# JHZ-E01S-HW-Sensor-H-I-S0_1.net
KiCad netlist of a schematic drawn in Altium Designer
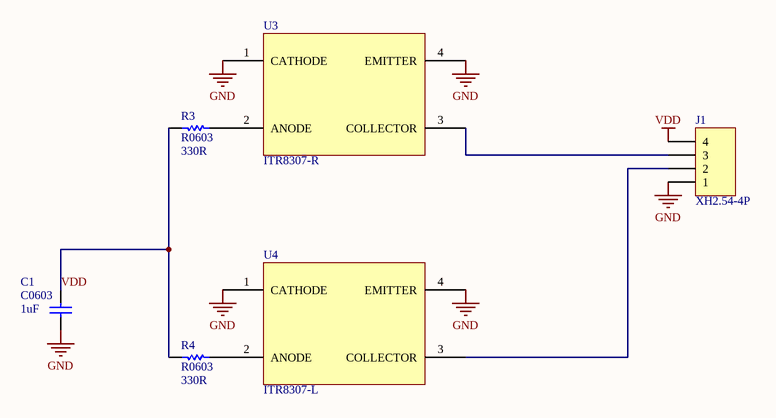
[diagram p0: JHZ-E01S-HW-Sensor-H-I-S0.1.SchDoc]

(export (version "E")
  (design (tool "Eeschema 10.0.6"))
  (components
    (comp (ref "C1")
      (value "C0603")
      (footprint "C0603_M1608")
      (description "Capacitor")
      (fields (field (name "ALTIUM_VALUE") "1uF") (field (name "PUBLISHER") "Altium Limited"))
      (libsource (lib "Miscellaneous Devices") (part "Cap"))
    )
    (comp (ref "J1")
      (value "XH2.54-4P")
      (footprint "PH-AWB-4P")
      (description "插座XH2.54-4P")
      (fields (field (name "Comment") "PH-AWB-4P") (field (name "PUBLISHER") "Altium Limited"))
      (libsource (lib "Liyao原理图库") (part "XH2.54-4P"))
    )
    (comp (ref "R3")
      (value "R0603")
      (description "Resistor")
      (fields (field (name "ALTIUM_VALUE") "330R") (field (name "PUBLISHER") "Altium Limited"))
      (libsource (lib "Miscellaneous Devices") (part "Res1"))
    )
    (comp (ref "R4")
      (value "R0603")
      (description "Resistor")
      (fields (field (name "ALTIUM_VALUE") "330R") (field (name "PUBLISHER") "Altium Limited"))
      (libsource (lib "Miscellaneous Devices") (part "Res1"))
    )
    (comp (ref "U3") (value "ITR8307-R") (footprint "ITR8307") (libsource (lib "光电管") (part "Component_1")))
    (comp (ref "U4") (value "ITR8307-L") (footprint "ITR8307") (libsource (lib "光电管") (part "Component_1")))
  )
  (nets
    (net (code "1") (name "GND") (class "Default")
      (node (ref "C1") (pin "2") (pinfunction "2_2") (pintype "passive"))
      (node (ref "J1") (pin "1") (pinfunction "1_1") (pintype "passive"))
      (node (ref "U3") (pin "1") (pinfunction "CATHODE_1") (pintype "passive"))
      (node (ref "U3") (pin "4") (pinfunction "EMITTER_4") (pintype "passive"))
      (node (ref "U4") (pin "1") (pinfunction "CATHODE_1") (pintype "passive"))
      (node (ref "U4") (pin "4") (pinfunction "EMITTER_4") (pintype "passive"))
    )
    (net (code "2") (name "Net-(U3-ANODE)") (class "Default")
      (node (ref "R3") (pin "1") (pinfunction "1_1") (pintype "passive"))
      (node (ref "U3") (pin "2") (pinfunction "ANODE_2") (pintype "passive"))
    )
    (net (code "3") (name "Net-(U3-COLLECTOR)") (class "Default")
      (node (ref "J1") (pin "3") (pinfunction "3_3") (pintype "passive"))
      (node (ref "U3") (pin "3") (pinfunction "COLLECTOR_3") (pintype "passive"))
    )
    (net (code "4") (name "Net-(U4-ANODE)") (class "Default")
      (node (ref "R4") (pin "1") (pinfunction "1_1") (pintype "passive"))
      (node (ref "U4") (pin "2") (pinfunction "ANODE_2") (pintype "passive"))
    )
    (net (code "5") (name "Net-(U4-COLLECTOR)") (class "Default")
      (node (ref "J1") (pin "2") (pinfunction "2_2") (pintype "passive"))
      (node (ref "U4") (pin "3") (pinfunction "COLLECTOR_3") (pintype "passive"))
    )
    (net (code "6") (name "VDD") (class "Default")
      (node (ref "C1") (pin "1") (pinfunction "1_1") (pintype "passive"))
      (node (ref "J1") (pin "4") (pinfunction "4_4") (pintype "passive"))
      (node (ref "R3") (pin "2") (pinfunction "2_2") (pintype "passive"))
      (node (ref "R4") (pin "2") (pinfunction "2_2") (pintype "passive"))
    )
  )
)
